# dmx-featherwing-v1.net
KiCad netlist of a schematic drawn in EAGLE
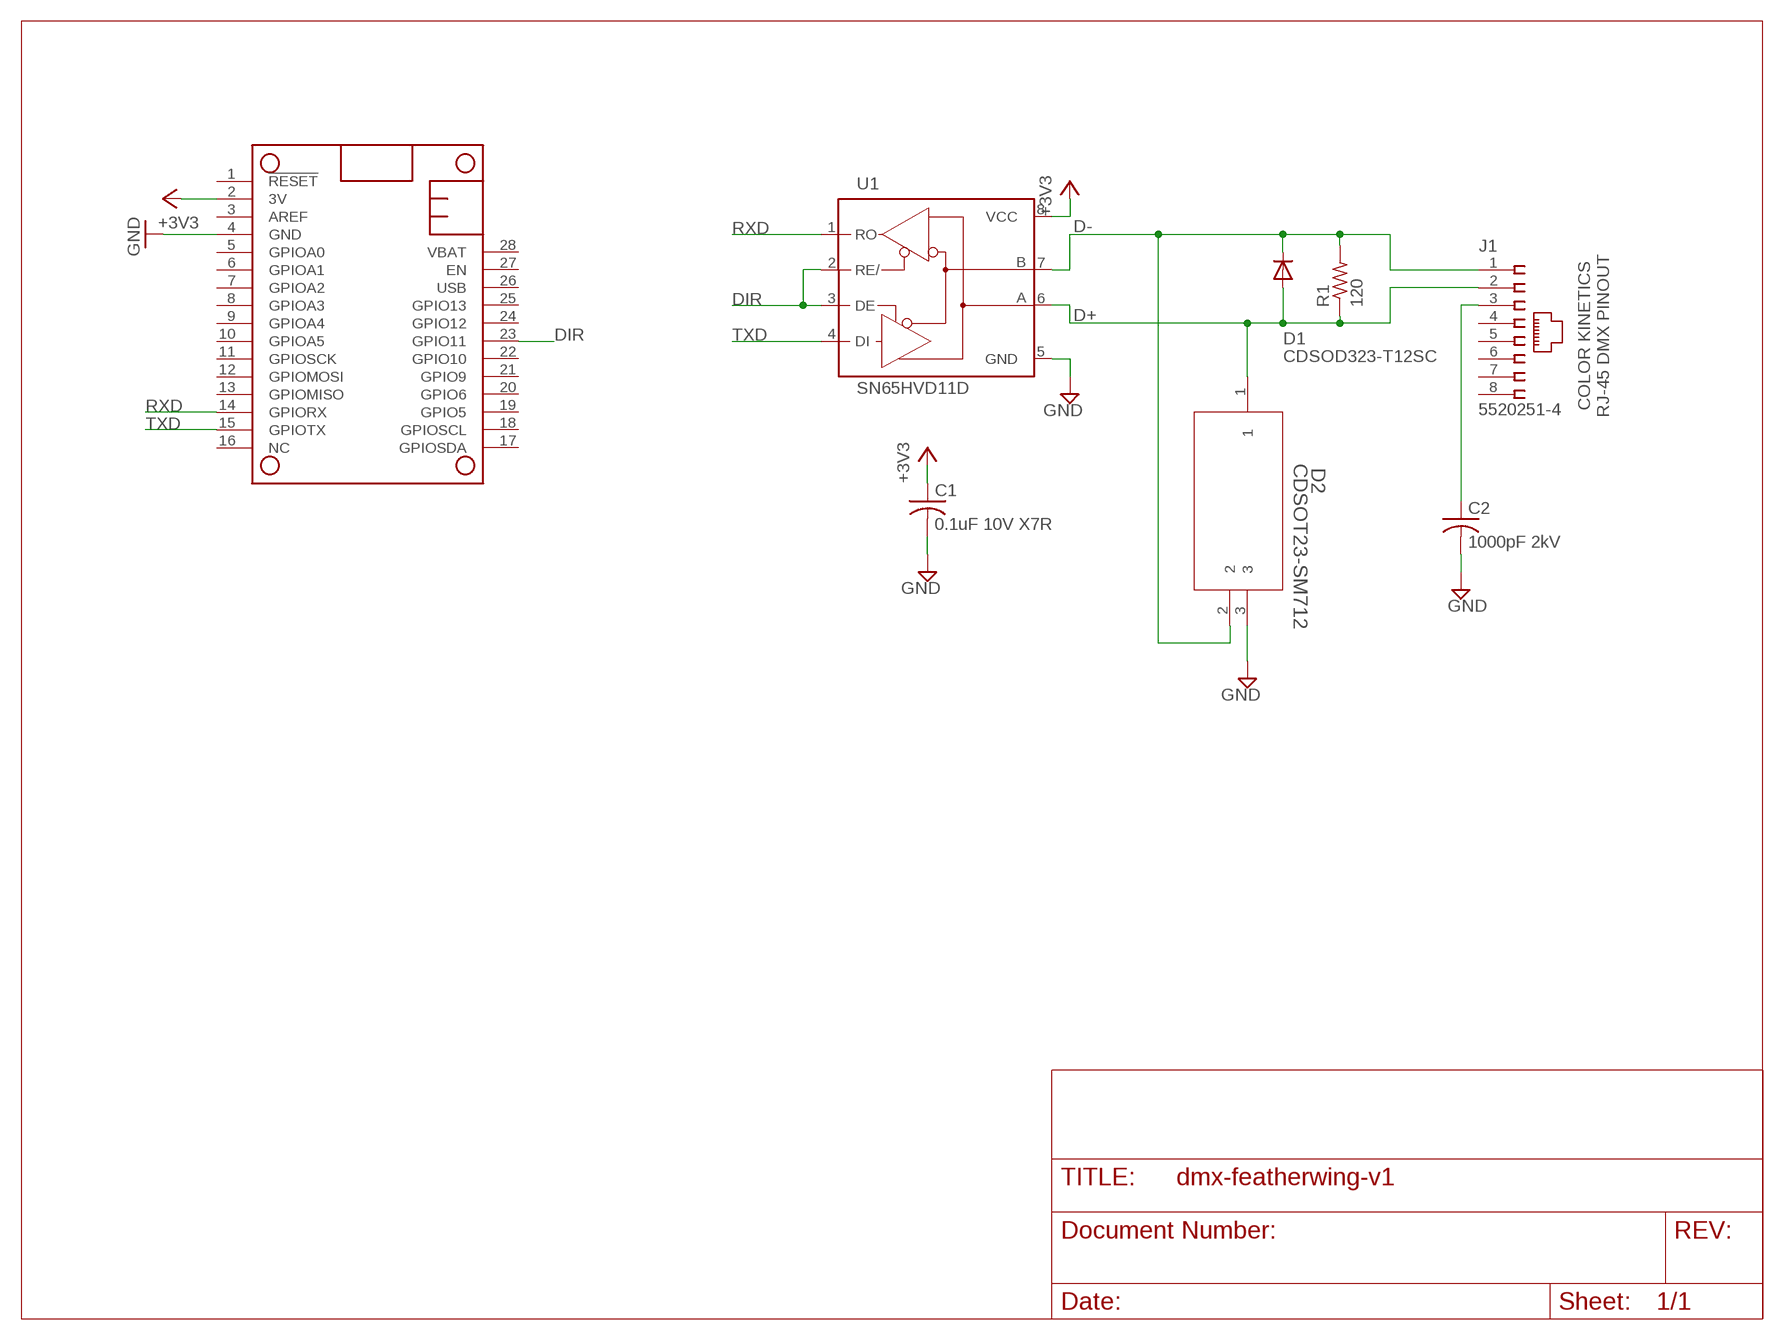
[diagram p0: schematic, sheet 1]

(export (version "E")
  (design (tool "Eeschema 10.0.6"))
  (components
    (comp (ref "C1")
      (value "0.1uF 10V X7R")
      (footprint "eagle-import:C0805")
      (libsource (lib "eagle-import") (part "C-USC0805"))
    )
    (comp (ref "C2")
      (value "1000pF 2kV")
      (footprint "eagle-import:C1206K")
      (libsource (lib "eagle-import") (part "C-USC1206K"))
    )
    (comp (ref "D1")
      (value "CDSOD323-T12SC")
      (footprint "eagle-import:SOD323-W")
      (libsource (lib "eagle-import") (part "DIODE-SOD323-W"))
    )
    (comp (ref "D2")
      (value "CDSOT23-SM712")
      (footprint "eagle-import:SOT_SM712")
      (libsource (lib "eagle-import") (part "CDSOT23-SM712"))
    )
    (comp (ref "J1")
      (value "5520251-4")
      (footprint "eagle-import:5520251-4")
      (libsource (lib "eagle-import") (part "5520251-4"))
    )
    (comp (ref "MS2")
      (value "FEATHERWING")
      (footprint "eagle-import:FEATHERWING")
      (libsource (lib "eagle-import") (part "FEATHERWING"))
    )
    (comp (ref "R1")
      (value "120")
      (footprint "eagle-import:R0805")
      (libsource (lib "eagle-import") (part "R-US_R0805"))
    )
    (comp (ref "U1")
      (value "SN65HVD11D")
      (footprint "eagle-import:SO08")
      (fields (field (name "MPN") "MAX3468CSA+"))
      (libsource (lib "eagle-import") (part "MAX34SA68C"))
    )
  )
  (nets
    (net (code "1") (name "+3V3") (class "Default")
      (node (ref "C1") (pin "1") (pinfunction "1_1") (pintype "passive"))
      (node (ref "MS2") (pin "2") (pinfunction "3V_2") (pintype "power_in"))
      (node (ref "U1") (pin "8") (pinfunction "VCC_8") (pintype "power_in"))
    )
    (net (code "2") (name "/D+") (class "Default")
      (node (ref "D1") (pin "A") (pinfunction "A_A") (pintype "passive"))
      (node (ref "D2") (pin "1") (pinfunction "1_1") (pintype "passive"))
      (node (ref "J1") (pin "2") (pinfunction "2_2") (pintype "passive"))
      (node (ref "R1") (pin "1") (pinfunction "1_1") (pintype "passive"))
      (node (ref "U1") (pin "6") (pinfunction "A_6") (pintype "passive"))
    )
    (net (code "3") (name "/D-") (class "Default")
      (node (ref "D1") (pin "C") (pinfunction "C_C") (pintype "passive"))
      (node (ref "D2") (pin "2") (pinfunction "2_2") (pintype "passive"))
      (node (ref "J1") (pin "1") (pinfunction "1_1") (pintype "passive"))
      (node (ref "R1") (pin "2") (pinfunction "2_2") (pintype "passive"))
      (node (ref "U1") (pin "7") (pinfunction "B_7") (pintype "passive"))
    )
    (net (code "4") (name "/DIR") (class "Default")
      (node (ref "MS2") (pin "23") (pinfunction "GPIO11_23") (pintype "bidirectional"))
      (node (ref "U1") (pin "2") (pinfunction "RE/_2") (pintype "input"))
      (node (ref "U1") (pin "3") (pinfunction "DE_3") (pintype "input"))
    )
    (net (code "5") (name "/RXD") (class "Default")
      (node (ref "MS2") (pin "14") (pinfunction "GPIORX_14") (pintype "bidirectional"))
      (node (ref "U1") (pin "1") (pinfunction "RO_1") (pintype "output"))
    )
    (net (code "6") (name "/TXD") (class "Default")
      (node (ref "MS2") (pin "15") (pinfunction "GPIOTX_15") (pintype "bidirectional"))
      (node (ref "U1") (pin "4") (pinfunction "DI_4") (pintype "input"))
    )
    (net (code "7") (name "/USB") (class "Default")
      (node (ref "MS2") (pin "26") (pinfunction "USB_26") (pintype "power_in"))
    )
    (net (code "8") (name "/VBAT") (class "Default")
      (node (ref "MS2") (pin "28") (pinfunction "VBAT_28") (pintype "power_in"))
    )
    (net (code "9") (name "GND") (class "Default")
      (node (ref "C1") (pin "2") (pinfunction "2_2") (pintype "passive"))
      (node (ref "C2") (pin "2") (pinfunction "2_2") (pintype "passive"))
      (node (ref "D2") (pin "3") (pinfunction "3_3") (pintype "passive"))
      (node (ref "MS2") (pin "4") (pinfunction "GND_4") (pintype "power_in"))
      (node (ref "U1") (pin "5") (pinfunction "GND_5") (pintype "power_in"))
    )
    (net (code "10") (name "Net-(C2-Pad1)") (class "Default")
      (node (ref "C2") (pin "1") (pinfunction "1_1") (pintype "passive"))
      (node (ref "J1") (pin "3") (pinfunction "3_3") (pintype "passive"))
    )
    (net (code "11") (name "unconnected-(J1-Pad4)") (class "Default")
      (node (ref "J1") (pin "4") (pinfunction "4_4") (pintype "passive"))
    )
    (net (code "12") (name "unconnected-(J1-Pad5)") (class "Default")
      (node (ref "J1") (pin "5") (pinfunction "5_5") (pintype "passive"))
    )
    (net (code "13") (name "unconnected-(J1-Pad6)") (class "Default")
      (node (ref "J1") (pin "6") (pinfunction "6_6") (pintype "passive"))
    )
    (net (code "14") (name "unconnected-(J1-Pad7)") (class "Default")
      (node (ref "J1") (pin "7") (pinfunction "7_7") (pintype "passive"))
    )
    (net (code "15") (name "unconnected-(J1-Pad8)") (class "Default")
      (node (ref "J1") (pin "8") (pinfunction "8_8") (pintype "passive"))
    )
    (net (code "16") (name "unconnected-(MS2-AREF-Pad3)") (class "Default")
      (node (ref "MS2") (pin "3") (pinfunction "AREF_3") (pintype "passive"))
    )
    (net (code "17") (name "unconnected-(MS2-EN-Pad27)") (class "Default")
      (node (ref "MS2") (pin "27") (pinfunction "EN_27") (pintype "passive"))
    )
    (net (code "18") (name "unconnected-(MS2-GPIO5-Pad19)") (class "Default")
      (node (ref "MS2") (pin "19") (pinfunction "GPIO5_19") (pintype "bidirectional"))
    )
    (net (code "19") (name "unconnected-(MS2-GPIO6-Pad20)") (class "Default")
      (node (ref "MS2") (pin "20") (pinfunction "GPIO6_20") (pintype "bidirectional"))
    )
    (net (code "20") (name "unconnected-(MS2-GPIO9-Pad21)") (class "Default")
      (node (ref "MS2") (pin "21") (pinfunction "GPIO9_21") (pintype "bidirectional"))
    )
    (net (code "21") (name "unconnected-(MS2-GPIO10-Pad22)") (class "Default")
      (node (ref "MS2") (pin "22") (pinfunction "GPIO10_22") (pintype "bidirectional"))
    )
    (net (code "22") (name "unconnected-(MS2-GPIO12-Pad24)") (class "Default")
      (node (ref "MS2") (pin "24") (pinfunction "GPIO12_24") (pintype "bidirectional"))
    )
    (net (code "23") (name "unconnected-(MS2-GPIO13-Pad25)") (class "Default")
      (node (ref "MS2") (pin "25") (pinfunction "GPIO13_25") (pintype "bidirectional"))
    )
    (net (code "24") (name "unconnected-(MS2-GPIOA0-Pad5)") (class "Default")
      (node (ref "MS2") (pin "5") (pinfunction "GPIOA0_5") (pintype "bidirectional"))
    )
    (net (code "25") (name "unconnected-(MS2-GPIOA1-Pad6)") (class "Default")
      (node (ref "MS2") (pin "6") (pinfunction "GPIOA1_6") (pintype "bidirectional"))
    )
    (net (code "26") (name "unconnected-(MS2-GPIOA2-Pad7)") (class "Default")
      (node (ref "MS2") (pin "7") (pinfunction "GPIOA2_7") (pintype "bidirectional"))
    )
    (net (code "27") (name "unconnected-(MS2-GPIOA3-Pad8)") (class "Default")
      (node (ref "MS2") (pin "8") (pinfunction "GPIOA3_8") (pintype "bidirectional"))
    )
    (net (code "28") (name "unconnected-(MS2-GPIOA4-Pad9)") (class "Default")
      (node (ref "MS2") (pin "9") (pinfunction "GPIOA4_9") (pintype "bidirectional"))
    )
    (net (code "29") (name "unconnected-(MS2-GPIOA5-Pad10)") (class "Default")
      (node (ref "MS2") (pin "10") (pinfunction "GPIOA5_10") (pintype "bidirectional"))
    )
    (net (code "30") (name "unconnected-(MS2-GPIOMISO-Pad13)") (class "Default")
      (node (ref "MS2") (pin "13") (pinfunction "GPIOMISO_13") (pintype "bidirectional"))
    )
    (net (code "31") (name "unconnected-(MS2-GPIOMOSI-Pad12)") (class "Default")
      (node (ref "MS2") (pin "12") (pinfunction "GPIOMOSI_12") (pintype "bidirectional"))
    )
    (net (code "32") (name "unconnected-(MS2-GPIOSCK-Pad11)") (class "Default")
      (node (ref "MS2") (pin "11") (pinfunction "GPIOSCK_11") (pintype "bidirectional"))
    )
    (net (code "33") (name "unconnected-(MS2-GPIOSCL-Pad18)") (class "Default")
      (node (ref "MS2") (pin "18") (pinfunction "GPIOSCL_18") (pintype "bidirectional"))
    )
    (net (code "34") (name "unconnected-(MS2-GPIOSDA-Pad17)") (class "Default")
      (node (ref "MS2") (pin "17") (pinfunction "GPIOSDA_17") (pintype "bidirectional"))
    )
    (net (code "35") (name "unconnected-(MS2-NC-Pad16)") (class "Default")
      (node (ref "MS2") (pin "16") (pinfunction "NC_16") (pintype "passive"))
    )
    (net (code "36") (name "unconnected-(MS2-~{RESET}-Pad1)") (class "Default")
      (node (ref "MS2") (pin "1") (pinfunction "~{RESET}_1") (pintype "input"))
    )
  )
)
